# SPosition.net
KiCad netlist of a schematic drawn in EAGLE
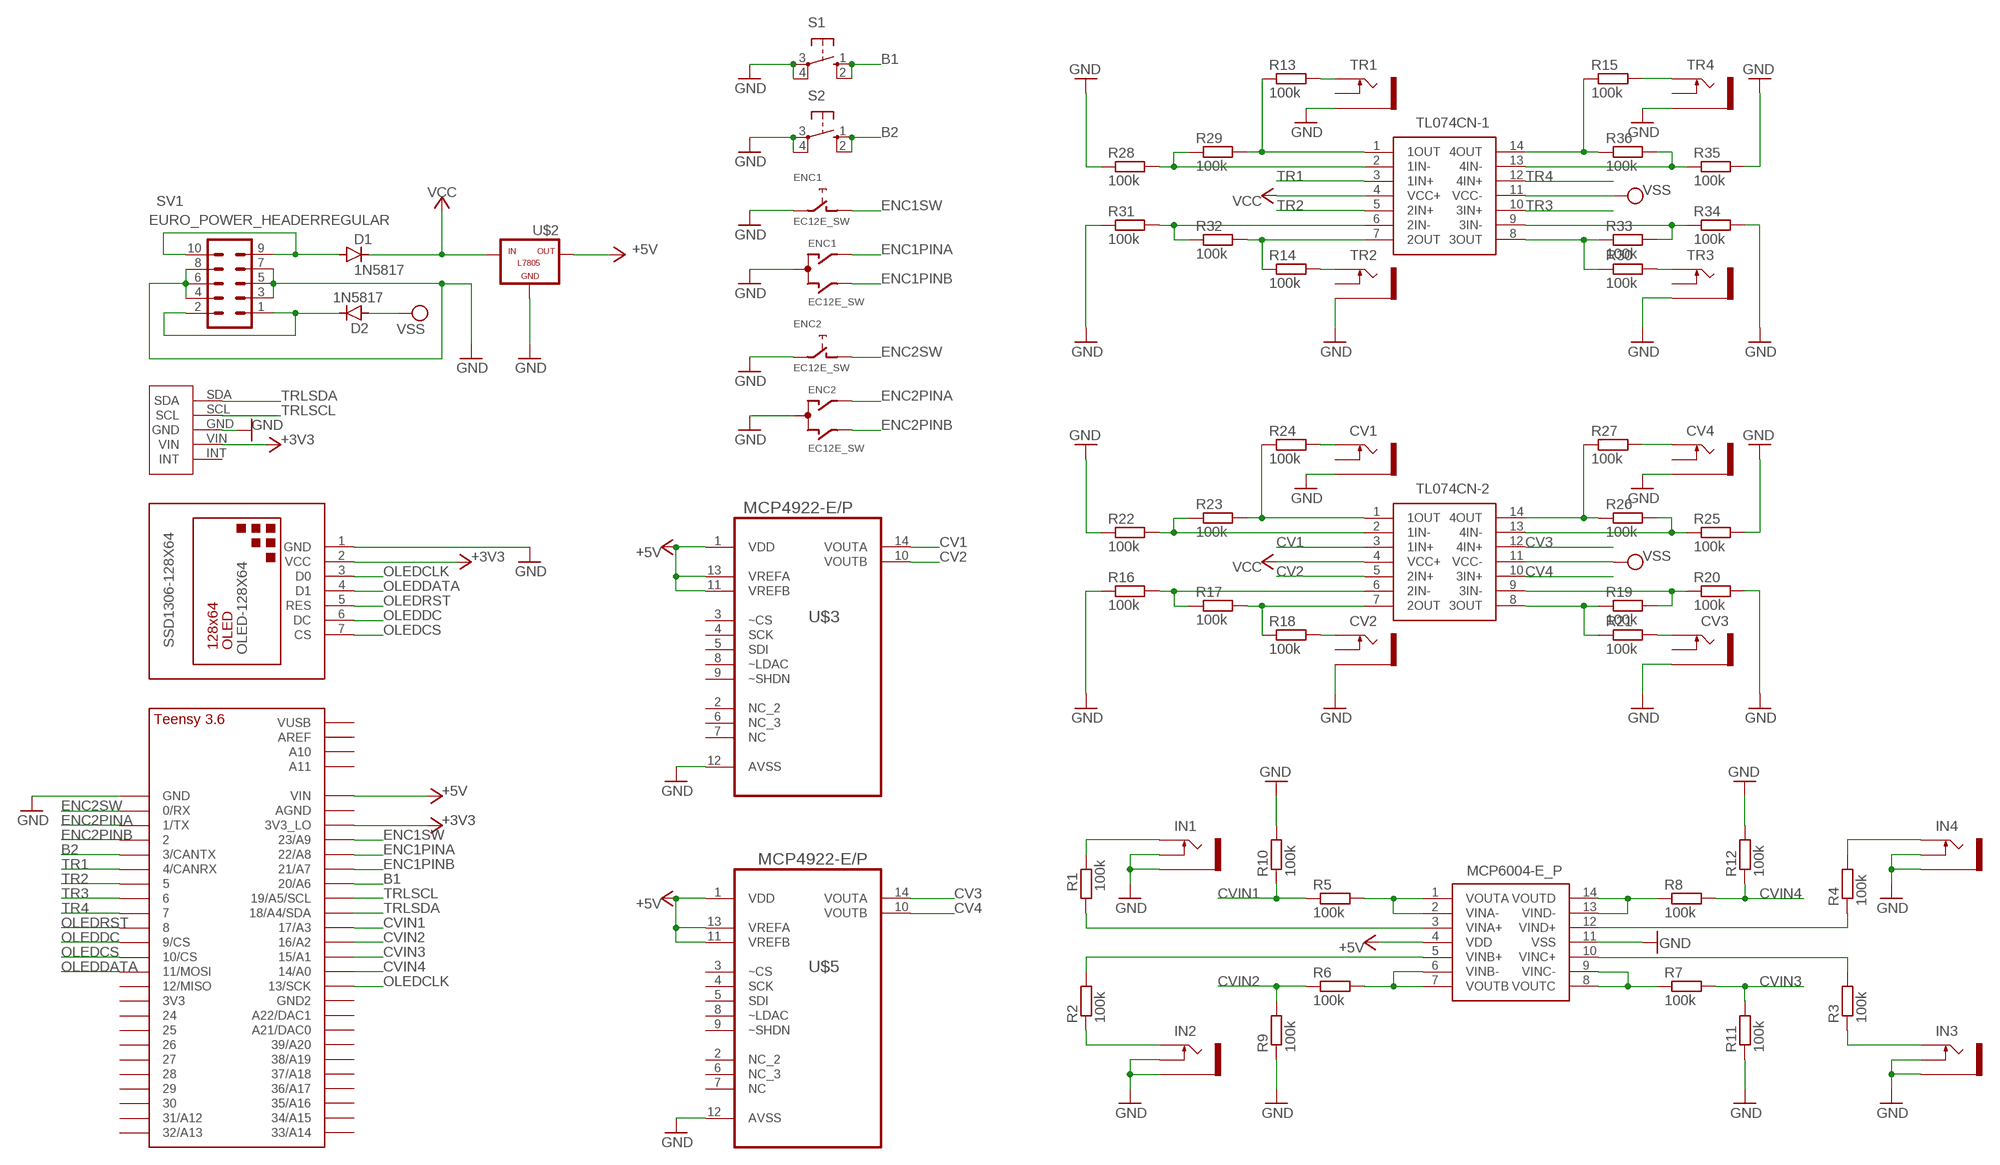
[diagram p0: schematic, sheet 1]

(export (version "E")
  (design (tool "Eeschema 10.0.6"))
  (components
    (comp (ref "CV1")
      (value "THONKICONNNEW")
      (footprint "eagle-import:WQP-PJ301M-12_JACK")
      (libsource (lib "eagle-import") (part "THONKICONNNEW"))
    )
    (comp (ref "CV2")
      (value "THONKICONNNEW")
      (footprint "eagle-import:WQP-PJ301M-12_JACK")
      (libsource (lib "eagle-import") (part "THONKICONNNEW"))
    )
    (comp (ref "CV3")
      (value "THONKICONNNEW")
      (footprint "eagle-import:WQP-PJ301M-12_JACK")
      (libsource (lib "eagle-import") (part "THONKICONNNEW"))
    )
    (comp (ref "CV4")
      (value "THONKICONNNEW")
      (footprint "eagle-import:WQP-PJ301M-12_JACK")
      (libsource (lib "eagle-import") (part "THONKICONNNEW"))
    )
    (comp (ref "D1")
      (value "1N5817")
      (footprint "eagle-import:DO41-10")
      (libsource (lib "eagle-import") (part "1N4004"))
    )
    (comp (ref "D2")
      (value "1N5817")
      (footprint "eagle-import:DO41-10")
      (libsource (lib "eagle-import") (part "1N4004"))
    )
    (comp (ref "ENC1")
      (value "EC12E_SW")
      (footprint "eagle-import:ALPS_EC12E_SW")
      (fields (field (name "MPN") "EC12E2424407"))
      (libsource (lib "eagle-import") (part "EC12E_SW"))
    )
    (comp (ref "ENC2")
      (value "EC12E_SW")
      (footprint "eagle-import:ALPS_EC12E_SW")
      (fields (field (name "MPN") "EC12E2424407"))
      (libsource (lib "eagle-import") (part "EC12E_SW"))
    )
    (comp (ref "IN1")
      (value "THONKICONNNEW")
      (footprint "eagle-import:WQP-PJ301M-12_JACK")
      (libsource (lib "eagle-import") (part "THONKICONNNEW"))
    )
    (comp (ref "IN2")
      (value "THONKICONNNEW")
      (footprint "eagle-import:WQP-PJ301M-12_JACK")
      (libsource (lib "eagle-import") (part "THONKICONNNEW"))
    )
    (comp (ref "IN3")
      (value "THONKICONNNEW")
      (footprint "eagle-import:WQP-PJ301M-12_JACK")
      (libsource (lib "eagle-import") (part "THONKICONNNEW"))
    )
    (comp (ref "IN4")
      (value "THONKICONNNEW")
      (footprint "eagle-import:WQP-PJ301M-12_JACK")
      (libsource (lib "eagle-import") (part "THONKICONNNEW"))
    )
    (comp (ref "MCP6004-E_P")
      (value "MCP6004-E_P")
      (footprint "eagle-import:DIP781W56P254L1918H533Q14N")
      (fields
        (field (name "MANUFACTURER_PART_NUMBER") "mcp6004-e/p")
        (field (name "MOUSER_PART_NUMBER") "579-MCP6004-E/P")
        (field (name "RS_PART_NUMBER") "7386178P")
      )
      (libsource (lib "eagle-import") (part "MCP6004-E_P"))
    )
    (comp (ref "R1")
      (value "100k")
      (footprint "eagle-import:R0805")
      (libsource (lib "eagle-import") (part "R-EU_R0805"))
    )
    (comp (ref "R2")
      (value "100k")
      (footprint "eagle-import:R0805")
      (libsource (lib "eagle-import") (part "R-EU_R0805"))
    )
    (comp (ref "R3")
      (value "100k")
      (footprint "eagle-import:R0805")
      (libsource (lib "eagle-import") (part "R-EU_R0805"))
    )
    (comp (ref "R4")
      (value "100k")
      (footprint "eagle-import:R0805")
      (libsource (lib "eagle-import") (part "R-EU_R0805"))
    )
    (comp (ref "R5")
      (value "100k")
      (footprint "eagle-import:R0805")
      (libsource (lib "eagle-import") (part "R-EU_R0805"))
    )
    (comp (ref "R6")
      (value "100k")
      (footprint "eagle-import:R0805")
      (libsource (lib "eagle-import") (part "R-EU_R0805"))
    )
    (comp (ref "R7")
      (value "100k")
      (footprint "eagle-import:R0805")
      (libsource (lib "eagle-import") (part "R-EU_R0805"))
    )
    (comp (ref "R8")
      (value "100k")
      (footprint "eagle-import:R0805")
      (libsource (lib "eagle-import") (part "R-EU_R0805"))
    )
    (comp (ref "R9")
      (value "100k")
      (footprint "eagle-import:R0805")
      (libsource (lib "eagle-import") (part "R-EU_R0805"))
    )
    (comp (ref "R10")
      (value "100k")
      (footprint "eagle-import:R0805")
      (libsource (lib "eagle-import") (part "R-EU_R0805"))
    )
    (comp (ref "R11")
      (value "100k")
      (footprint "eagle-import:R0805")
      (libsource (lib "eagle-import") (part "R-EU_R0805"))
    )
    (comp (ref "R12")
      (value "100k")
      (footprint "eagle-import:R0805")
      (libsource (lib "eagle-import") (part "R-EU_R0805"))
    )
    (comp (ref "R13")
      (value "100k")
      (footprint "eagle-import:R0805")
      (libsource (lib "eagle-import") (part "R-EU_R0805"))
    )
    (comp (ref "R14")
      (value "100k")
      (footprint "eagle-import:R0805")
      (libsource (lib "eagle-import") (part "R-EU_R0805"))
    )
    (comp (ref "R15")
      (value "100k")
      (footprint "eagle-import:R0805")
      (libsource (lib "eagle-import") (part "R-EU_R0805"))
    )
    (comp (ref "R16")
      (value "100k")
      (footprint "eagle-import:R0805")
      (libsource (lib "eagle-import") (part "R-EU_R0805"))
    )
    (comp (ref "R17")
      (value "100k")
      (footprint "eagle-import:R0805")
      (libsource (lib "eagle-import") (part "R-EU_R0805"))
    )
    (comp (ref "R18")
      (value "100k")
      (footprint "eagle-import:R0805")
      (libsource (lib "eagle-import") (part "R-EU_R0805"))
    )
    (comp (ref "R19")
      (value "100k")
      (footprint "eagle-import:R0805")
      (libsource (lib "eagle-import") (part "R-EU_R0805"))
    )
    (comp (ref "R20")
      (value "100k")
      (footprint "eagle-import:R0805")
      (libsource (lib "eagle-import") (part "R-EU_R0805"))
    )
    (comp (ref "R21")
      (value "100k")
      (footprint "eagle-import:R0805")
      (libsource (lib "eagle-import") (part "R-EU_R0805"))
    )
    (comp (ref "R22")
      (value "100k")
      (footprint "eagle-import:R0805")
      (libsource (lib "eagle-import") (part "R-EU_R0805"))
    )
    (comp (ref "R23")
      (value "100k")
      (footprint "eagle-import:R0805")
      (libsource (lib "eagle-import") (part "R-EU_R0805"))
    )
    (comp (ref "R24")
      (value "100k")
      (footprint "eagle-import:R0805")
      (libsource (lib "eagle-import") (part "R-EU_R0805"))
    )
    (comp (ref "R25")
      (value "100k")
      (footprint "eagle-import:R0805")
      (libsource (lib "eagle-import") (part "R-EU_R0805"))
    )
    (comp (ref "R26")
      (value "100k")
      (footprint "eagle-import:R0805")
      (libsource (lib "eagle-import") (part "R-EU_R0805"))
    )
    (comp (ref "R27")
      (value "100k")
      (footprint "eagle-import:R0805")
      (libsource (lib "eagle-import") (part "R-EU_R0805"))
    )
    (comp (ref "R28")
      (value "100k")
      (footprint "eagle-import:R0805")
      (libsource (lib "eagle-import") (part "R-EU_R0805"))
    )
    (comp (ref "R29")
      (value "100k")
      (footprint "eagle-import:R0805")
      (libsource (lib "eagle-import") (part "R-EU_R0805"))
    )
    (comp (ref "R30")
      (value "100k")
      (footprint "eagle-import:R0805")
      (libsource (lib "eagle-import") (part "R-EU_R0805"))
    )
    (comp (ref "R31")
      (value "100k")
      (footprint "eagle-import:R0805")
      (libsource (lib "eagle-import") (part "R-EU_R0805"))
    )
    (comp (ref "R32")
      (value "100k")
      (footprint "eagle-import:R0805")
      (libsource (lib "eagle-import") (part "R-EU_R0805"))
    )
    (comp (ref "R33")
      (value "100k")
      (footprint "eagle-import:R0805")
      (libsource (lib "eagle-import") (part "R-EU_R0805"))
    )
    (comp (ref "R34")
      (value "100k")
      (footprint "eagle-import:R0805")
      (libsource (lib "eagle-import") (part "R-EU_R0805"))
    )
    (comp (ref "R35")
      (value "100k")
      (footprint "eagle-import:R0805")
      (libsource (lib "eagle-import") (part "R-EU_R0805"))
    )
    (comp (ref "R36")
      (value "100k")
      (footprint "eagle-import:R0805")
      (libsource (lib "eagle-import") (part "R-EU_R0805"))
    )
    (comp (ref "S1")
      (value "10-XX")
      (footprint "eagle-import:B3F-10XX")
      (fields (field (name "MPN") "B3F-1000"))
      (libsource (lib "eagle-import") (part "10-XX"))
    )
    (comp (ref "S2")
      (value "10-XX")
      (footprint "eagle-import:B3F-10XX")
      (fields (field (name "MPN") "B3F-1000"))
      (libsource (lib "eagle-import") (part "10-XX"))
    )
    (comp (ref "SSD1306-128X64")
      (value "OLED-128X64")
      (footprint "eagle-import:DISPLAY-OLED-128X64-SMALL")
      (libsource (lib "eagle-import") (part "OLED-128X64"))
    )
    (comp (ref "SV1")
      (value "EURO_POWER_HEADERREGULAR")
      (footprint "eagle-import:EURO_POWER_HEADER")
      (libsource (lib "eagle-import") (part "EURO_POWER_HEADERREGULAR"))
    )
    (comp (ref "TL074CN-1")
      (value "TL074CN")
      (footprint "eagle-import:DIP794W53P254L1930H508Q14N")
      (fields (field (name "MOUSER_PART_NUMBER") "595-TL074CN") (field (name "RS_PART_NUMBER") "0302621P"))
      (libsource (lib "eagle-import") (part "TL074CN"))
    )
    (comp (ref "TL074CN-2")
      (value "TL074CN")
      (footprint "eagle-import:DIP794W53P254L1930H508Q14N")
      (fields (field (name "MOUSER_PART_NUMBER") "595-TL074CN") (field (name "RS_PART_NUMBER") "0302621P"))
      (libsource (lib "eagle-import") (part "TL074CN"))
    )
    (comp (ref "TR1")
      (value "THONKICONNNEW")
      (footprint "eagle-import:WQP-PJ301M-12_JACK")
      (libsource (lib "eagle-import") (part "THONKICONNNEW"))
    )
    (comp (ref "TR2")
      (value "THONKICONNNEW")
      (footprint "eagle-import:WQP-PJ301M-12_JACK")
      (libsource (lib "eagle-import") (part "THONKICONNNEW"))
    )
    (comp (ref "TR3")
      (value "THONKICONNNEW")
      (footprint "eagle-import:WQP-PJ301M-12_JACK")
      (libsource (lib "eagle-import") (part "THONKICONNNEW"))
    )
    (comp (ref "TR4")
      (value "THONKICONNNEW")
      (footprint "eagle-import:WQP-PJ301M-12_JACK")
      (libsource (lib "eagle-import") (part "THONKICONNNEW"))
    )
    (comp (ref "U$1")
      (value "TEENSY_3.5/3.6_BASIC")
      (footprint "eagle-import:TEENSY_3.5_3.6_BASIC")
      (libsource (lib "eagle-import") (part "TEENSY_3.5/3.6_BASIC"))
    )
    (comp (ref "U$2")
      (value "-L7805")
      (footprint "eagle-import:L7805")
      (libsource (lib "eagle-import") (part "-L7805"))
    )
    (comp (ref "U$3")
      (value "MCP4922-E/P")
      (footprint "eagle-import:DIP254P762X533-14")
      (fields (field (name "MF") "Microchip"))
      (libsource (lib "eagle-import") (part "MCP4922-E/P"))
    )
    (comp (ref "U$4")
      (value "SUPERPOSITION")
      (footprint "eagle-import:SUPERPOSITION")
      (libsource (lib "eagle-import") (part "SUPERPOSITION"))
    )
    (comp (ref "U$5")
      (value "MCP4922-E/P")
      (footprint "eagle-import:DIP254P762X533-14")
      (fields (field (name "MF") "Microchip"))
      (libsource (lib "eagle-import") (part "MCP4922-E/P"))
    )
  )
  (nets
    (net (code "1") (name "+3V3") (class "Default")
      (node (ref "SSD1306-128X64") (pin "2") (pinfunction "VCC_2") (pintype "power_in"))
      (node (ref "U$1") (pin "3V3_LO") (pinfunction "3V3_LO_3V3_LO") (pintype "bidirectional"))
      (node (ref "U$4") (pin "VIN") (pinfunction "VIN_VIN") (pintype "bidirectional"))
    )
    (net (code "2") (name "+5V") (class "Default")
      (node (ref "MCP6004-E_P") (pin "4") (pinfunction "VDD_4") (pintype "power_in"))
      (node (ref "U$1") (pin "VIN") (pinfunction "VIN_VIN") (pintype "bidirectional"))
      (node (ref "U$2") (pin "OUT") (pinfunction "OUT_OUT") (pintype "passive"))
      (node (ref "U$3") (pin "1") (pinfunction "VDD_1") (pintype "power_in"))
      (node (ref "U$3") (pin "11") (pinfunction "VREFB_11") (pintype "input"))
      (node (ref "U$3") (pin "13") (pinfunction "VREFA_13") (pintype "input"))
      (node (ref "U$5") (pin "1") (pinfunction "VDD_1") (pintype "power_in"))
      (node (ref "U$5") (pin "11") (pinfunction "VREFB_11") (pintype "input"))
      (node (ref "U$5") (pin "13") (pinfunction "VREFA_13") (pintype "input"))
    )
    (net (code "3") (name "/B1") (class "Default")
      (node (ref "S1") (pin "1") (pinfunction "S_1") (pintype "passive"))
      (node (ref "S1") (pin "2") (pinfunction "S1_2") (pintype "passive"))
      (node (ref "U$1") (pin "20/A6") (pinfunction "20/A6_20/A6") (pintype "bidirectional"))
    )
    (net (code "4") (name "/B2") (class "Default")
      (node (ref "S2") (pin "1") (pinfunction "S_1") (pintype "passive"))
      (node (ref "S2") (pin "2") (pinfunction "S1_2") (pintype "passive"))
      (node (ref "U$1") (pin "3/CANTX") (pinfunction "3/CANTX_3/CANTX") (pintype "bidirectional"))
    )
    (net (code "5") (name "/CV1") (class "Default")
      (node (ref "TL074CN-2") (pin "3") (pinfunction "1IN+_3") (pintype "input"))
      (node (ref "U$3") (pin "14") (pinfunction "VOUTA_14") (pintype "output"))
    )
    (net (code "6") (name "/CV2") (class "Default")
      (node (ref "TL074CN-2") (pin "5") (pinfunction "2IN+_5") (pintype "input"))
      (node (ref "U$3") (pin "10") (pinfunction "VOUTB_10") (pintype "output"))
    )
    (net (code "7") (name "/CV3") (class "Default")
      (node (ref "TL074CN-2") (pin "12") (pinfunction "4IN+_12") (pintype "input"))
      (node (ref "U$5") (pin "14") (pinfunction "VOUTA_14") (pintype "output"))
    )
    (net (code "8") (name "/CV4") (class "Default")
      (node (ref "TL074CN-2") (pin "10") (pinfunction "3IN+_10") (pintype "input"))
      (node (ref "U$5") (pin "10") (pinfunction "VOUTB_10") (pintype "output"))
    )
    (net (code "9") (name "/CVIN1") (class "Default")
      (node (ref "R10") (pin "1") (pinfunction "1_1") (pintype "passive"))
      (node (ref "R5") (pin "1") (pinfunction "1_1") (pintype "passive"))
      (node (ref "U$1") (pin "17/A3") (pinfunction "17/A3_17/A3") (pintype "bidirectional"))
    )
    (net (code "10") (name "/CVIN2") (class "Default")
      (node (ref "R6") (pin "1") (pinfunction "1_1") (pintype "passive"))
      (node (ref "R9") (pin "2") (pinfunction "2_2") (pintype "passive"))
      (node (ref "U$1") (pin "16/A2") (pinfunction "16/A2_16/A2") (pintype "bidirectional"))
    )
    (net (code "11") (name "/CVIN3") (class "Default")
      (node (ref "R11") (pin "2") (pinfunction "2_2") (pintype "passive"))
      (node (ref "R7") (pin "2") (pinfunction "2_2") (pintype "passive"))
      (node (ref "U$1") (pin "15/A1") (pinfunction "15/A1_15/A1") (pintype "bidirectional"))
    )
    (net (code "12") (name "/CVIN4") (class "Default")
      (node (ref "R12") (pin "1") (pinfunction "1_1") (pintype "passive"))
      (node (ref "R8") (pin "2") (pinfunction "2_2") (pintype "passive"))
      (node (ref "U$1") (pin "14/A0") (pinfunction "14/A0_14/A0") (pintype "bidirectional"))
    )
    (net (code "13") (name "/ENC1PINA") (class "Default")
      (node (ref "ENC1") (pin "A") (pinfunction "A_A") (pintype "passive"))
      (node (ref "U$1") (pin "22/A8") (pinfunction "22/A8_22/A8") (pintype "bidirectional"))
    )
    (net (code "14") (name "/ENC1PINB") (class "Default")
      (node (ref "ENC1") (pin "B") (pinfunction "B_B") (pintype "passive"))
      (node (ref "U$1") (pin "21/A7") (pinfunction "21/A7_21/A7") (pintype "bidirectional"))
    )
    (net (code "15") (name "/ENC1SW") (class "Default")
      (node (ref "ENC1") (pin "D") (pinfunction "1_D") (pintype "passive"))
      (node (ref "U$1") (pin "23/A9") (pinfunction "23/A9_23/A9") (pintype "bidirectional"))
    )
    (net (code "16") (name "/ENC2PINA") (class "Default")
      (node (ref "ENC2") (pin "A") (pinfunction "A_A") (pintype "passive"))
      (node (ref "U$1") (pin "1/TX") (pinfunction "1/TX_1/TX") (pintype "bidirectional"))
    )
    (net (code "17") (name "/ENC2PINB") (class "Default")
      (node (ref "ENC2") (pin "B") (pinfunction "B_B") (pintype "passive"))
      (node (ref "U$1") (pin "2") (pinfunction "2_2") (pintype "bidirectional"))
    )
    (net (code "18") (name "/ENC2SW") (class "Default")
      (node (ref "ENC2") (pin "D") (pinfunction "1_D") (pintype "passive"))
      (node (ref "U$1") (pin "0/RX") (pinfunction "0/RX_0/RX") (pintype "bidirectional"))
    )
    (net (code "19") (name "/OLEDCLK") (class "Default")
      (node (ref "SSD1306-128X64") (pin "3") (pinfunction "D0_3") (pintype "bidirectional"))
      (node (ref "U$1") (pin "13/SCK") (pinfunction "13/SCK_13/SCK") (pintype "bidirectional"))
    )
    (net (code "20") (name "/OLEDCS") (class "Default")
      (node (ref "SSD1306-128X64") (pin "7") (pinfunction "CS_7") (pintype "bidirectional"))
      (node (ref "U$1") (pin "10/CS") (pinfunction "10/CS_10/CS") (pintype "bidirectional"))
    )
    (net (code "21") (name "/OLEDDATA") (class "Default")
      (node (ref "SSD1306-128X64") (pin "4") (pinfunction "D1_4") (pintype "bidirectional"))
      (node (ref "U$1") (pin "11/MOSI") (pinfunction "11/MOSI_11/MOSI") (pintype "bidirectional"))
    )
    (net (code "22") (name "/OLEDDC") (class "Default")
      (node (ref "SSD1306-128X64") (pin "6") (pinfunction "DC_6") (pintype "bidirectional"))
      (node (ref "U$1") (pin "9/CS") (pinfunction "9/CS_9/CS") (pintype "bidirectional"))
    )
    (net (code "23") (name "/OLEDRST") (class "Default")
      (node (ref "SSD1306-128X64") (pin "5") (pinfunction "RES_5") (pintype "bidirectional"))
      (node (ref "U$1") (pin "8") (pinfunction "8_8") (pintype "bidirectional"))
    )
    (net (code "24") (name "/TR1") (class "Default")
      (node (ref "TL074CN-1") (pin "3") (pinfunction "1IN+_3") (pintype "input"))
      (node (ref "U$1") (pin "4/CANRX") (pinfunction "4/CANRX_4/CANRX") (pintype "bidirectional"))
    )
    (net (code "25") (name "/TR2") (class "Default")
      (node (ref "TL074CN-1") (pin "5") (pinfunction "2IN+_5") (pintype "input"))
      (node (ref "U$1") (pin "5") (pinfunction "5_5") (pintype "bidirectional"))
    )
    (net (code "26") (name "/TR3") (class "Default")
      (node (ref "TL074CN-1") (pin "10") (pinfunction "3IN+_10") (pintype "input"))
      (node (ref "U$1") (pin "6") (pinfunction "6_6") (pintype "bidirectional"))
    )
    (net (code "27") (name "/TR4") (class "Default")
      (node (ref "TL074CN-1") (pin "12") (pinfunction "4IN+_12") (pintype "input"))
      (node (ref "U$1") (pin "7") (pinfunction "7_7") (pintype "bidirectional"))
    )
    (net (code "28") (name "/TRLSCL") (class "Default")
      (node (ref "U$1") (pin "19/A5/SCL") (pinfunction "19/A5/SCL_19/A5/SCL") (pintype "bidirectional"))
      (node (ref "U$4") (pin "SCL") (pinfunction "SCL_SCL") (pintype "bidirectional"))
    )
    (net (code "29") (name "/TRLSDA") (class "Default")
      (node (ref "U$1") (pin "18/A4/SDA") (pinfunction "18/A4/SDA_18/A4/SDA") (pintype "bidirectional"))
      (node (ref "U$4") (pin "SDA") (pinfunction "SDA_SDA") (pintype "bidirectional"))
    )
    (net (code "30") (name "GND") (class "Default")
      (node (ref "CV1") (pin "P$3_SLEEVE") (pinfunction "SLEEVE_P$3_SLEEVE") (pintype "passive"))
      (node (ref "CV2") (pin "P$3_SLEEVE") (pinfunction "SLEEVE_P$3_SLEEVE") (pintype "passive"))
      (node (ref "CV3") (pin "P$3_SLEEVE") (pinfunction "SLEEVE_P$3_SLEEVE") (pintype "passive"))
      (node (ref "CV4") (pin "P$3_SLEEVE") (pinfunction "SLEEVE_P$3_SLEEVE") (pintype "passive"))
      (node (ref "ENC1") (pin "C") (pinfunction "C_C") (pintype "passive"))
      (node (ref "ENC1") (pin "E") (pinfunction "2_E") (pintype "passive"))
      (node (ref "ENC2") (pin "C") (pinfunction "C_C") (pintype "passive"))
      (node (ref "ENC2") (pin "E") (pinfunction "2_E") (pintype "passive"))
      (node (ref "IN1") (pin "P$2_SWITCH") (pinfunction "SWITCH_P$2_SWITCH") (pintype "passive"))
      (node (ref "IN1") (pin "P$3_SLEEVE") (pinfunction "SLEEVE_P$3_SLEEVE") (pintype "passive"))
      (node (ref "IN2") (pin "P$2_SWITCH") (pinfunction "SWITCH_P$2_SWITCH") (pintype "passive"))
      (node (ref "IN2") (pin "P$3_SLEEVE") (pinfunction "SLEEVE_P$3_SLEEVE") (pintype "passive"))
      (node (ref "IN3") (pin "P$2_SWITCH") (pinfunction "SWITCH_P$2_SWITCH") (pintype "passive"))
      (node (ref "IN3") (pin "P$3_SLEEVE") (pinfunction "SLEEVE_P$3_SLEEVE") (pintype "passive"))
      (node (ref "IN4") (pin "P$2_SWITCH") (pinfunction "SWITCH_P$2_SWITCH") (pintype "passive"))
      (node (ref "IN4") (pin "P$3_SLEEVE") (pinfunction "SLEEVE_P$3_SLEEVE") (pintype "passive"))
      (node (ref "MCP6004-E_P") (pin "11") (pinfunction "VSS_11") (pintype "power_in"))
      (node (ref "R10") (pin "2") (pinfunction "2_2") (pintype "passive"))
      (node (ref "R11") (pin "1") (pinfunction "1_1") (pintype "passive"))
      (node (ref "R12") (pin "2") (pinfunction "2_2") (pintype "passive"))
      (node (ref "R16") (pin "1") (pinfunction "1_1") (pintype "passive"))
      (node (ref "R20") (pin "2") (pinfunction "2_2") (pintype "passive"))
      (node (ref "R22") (pin "1") (pinfunction "1_1") (pintype "passive"))
      (node (ref "R25") (pin "2") (pinfunction "2_2") (pintype "passive"))
      (node (ref "R28") (pin "1") (pinfunction "1_1") (pintype "passive"))
      (node (ref "R31") (pin "1") (pinfunction "1_1") (pintype "passive"))
      (node (ref "R34") (pin "2") (pinfunction "2_2") (pintype "passive"))
      (node (ref "R35") (pin "2") (pinfunction "2_2") (pintype "passive"))
      (node (ref "R9") (pin "1") (pinfunction "1_1") (pintype "passive"))
      (node (ref "S1") (pin "3") (pinfunction "P_3") (pintype "passive"))
      (node (ref "S1") (pin "4") (pinfunction "P1_4") (pintype "passive"))
      (node (ref "S2") (pin "3") (pinfunction "P_3") (pintype "passive"))
      (node (ref "S2") (pin "4") (pinfunction "P1_4") (pintype "passive"))
      (node (ref "SSD1306-128X64") (pin "1") (pinfunction "GND_1") (pintype "power_in"))
      (node (ref "SV1") (pin "3") (pinfunction "3_3") (pintype "passive"))
      (node (ref "SV1") (pin "4") (pinfunction "4_4") (pintype "passive"))
      (node (ref "SV1") (pin "5") (pinfunction "5_5") (pintype "passive"))
      (node (ref "SV1") (pin "6") (pinfunction "6_6") (pintype "passive"))
      (node (ref "SV1") (pin "7") (pinfunction "7_7") (pintype "passive"))
      (node (ref "SV1") (pin "8") (pinfunction "8_8") (pintype "passive"))
      (node (ref "TR1") (pin "P$3_SLEEVE") (pinfunction "SLEEVE_P$3_SLEEVE") (pintype "passive"))
      (node (ref "TR2") (pin "P$3_SLEEVE") (pinfunction "SLEEVE_P$3_SLEEVE") (pintype "passive"))
      (node (ref "TR3") (pin "P$3_SLEEVE") (pinfunction "SLEEVE_P$3_SLEEVE") (pintype "passive"))
      (node (ref "TR4") (pin "P$3_SLEEVE") (pinfunction "SLEEVE_P$3_SLEEVE") (pintype "passive"))
      (node (ref "U$1") (pin "GND") (pinfunction "GND_GND") (pintype "bidirectional"))
      (node (ref "U$2") (pin "GND") (pinfunction "GND_GND") (pintype "input"))
      (node (ref "U$3") (pin "12") (pinfunction "AVSS_12") (pintype "power_in"))
      (node (ref "U$4") (pin "GND") (pinfunction "GND_GND") (pintype "bidirectional"))
      (node (ref "U$5") (pin "12") (pinfunction "AVSS_12") (pintype "power_in"))
    )
    (net (code "31") (name "Net-(CV1-TIP)") (class "Default")
      (node (ref "CV1") (pin "P$1_TIP") (pinfunction "TIP_P$1_TIP") (pintype "passive"))
      (node (ref "R24") (pin "2") (pinfunction "2_2") (pintype "passive"))
    )
    (net (code "32") (name "Net-(CV2-TIP)") (class "Default")
      (node (ref "CV2") (pin "P$1_TIP") (pinfunction "TIP_P$1_TIP") (pintype "passive"))
      (node (ref "R18") (pin "2") (pinfunction "2_2") (pintype "passive"))
    )
    (net (code "33") (name "Net-(CV3-TIP)") (class "Default")
      (node (ref "CV3") (pin "P$1_TIP") (pinfunction "TIP_P$1_TIP") (pintype "passive"))
      (node (ref "R21") (pin "2") (pinfunction "2_2") (pintype "passive"))
    )
    (net (code "34") (name "Net-(CV4-TIP)") (class "Default")
      (node (ref "CV4") (pin "P$1_TIP") (pinfunction "TIP_P$1_TIP") (pintype "passive"))
      (node (ref "R27") (pin "2") (pinfunction "2_2") (pintype "passive"))
    )
    (net (code "35") (name "Net-(D1-PadA)") (class "Default")
      (node (ref "D1") (pin "A") (pinfunction "A_A") (pintype "passive"))
      (node (ref "SV1") (pin "10") (pinfunction "10_10") (pintype "passive"))
      (node (ref "SV1") (pin "9") (pinfunction "9_9") (pintype "passive"))
    )
    (net (code "36") (name "Net-(D2-PadC)") (class "Default")
      (node (ref "D2") (pin "C") (pinfunction "C_C") (pintype "passive"))
      (node (ref "SV1") (pin "1") (pinfunction "1_1") (pintype "passive"))
      (node (ref "SV1") (pin "2") (pinfunction "2_2") (pintype "passive"))
    )
    (net (code "37") (name "Net-(IN1-TIP)") (class "Default")
      (node (ref "IN1") (pin "P$1_TIP") (pinfunction "TIP_P$1_TIP") (pintype "passive"))
      (node (ref "R1") (pin "2") (pinfunction "2_2") (pintype "passive"))
    )
    (net (code "38") (name "Net-(IN2-TIP)") (class "Default")
      (node (ref "IN2") (pin "P$1_TIP") (pinfunction "TIP_P$1_TIP") (pintype "passive"))
      (node (ref "R2") (pin "1") (pinfunction "1_1") (pintype "passive"))
    )
    (net (code "39") (name "Net-(IN3-TIP)") (class "Default")
      (node (ref "IN3") (pin "P$1_TIP") (pinfunction "TIP_P$1_TIP") (pintype "passive"))
      (node (ref "R3") (pin "1") (pinfunction "1_1") (pintype "passive"))
    )
    (net (code "40") (name "Net-(IN4-TIP)") (class "Default")
      (node (ref "IN4") (pin "P$1_TIP") (pinfunction "TIP_P$1_TIP") (pintype "passive"))
      (node (ref "R4") (pin "2") (pinfunction "2_2") (pintype "passive"))
    )
    (net (code "41") (name "Net-(MCP6004-E_P-VINA+)") (class "Default")
      (node (ref "MCP6004-E_P") (pin "3") (pinfunction "VINA+_3") (pintype "input"))
      (node (ref "R1") (pin "1") (pinfunction "1_1") (pintype "passive"))
    )
    (net (code "42") (name "Net-(MCP6004-E_P-VINA-)") (class "Default")
      (node (ref "MCP6004-E_P") (pin "1") (pinfunction "VOUTA_1") (pintype "output"))
      (node (ref "MCP6004-E_P") (pin "2") (pinfunction "VINA-_2") (pintype "input"))
      (node (ref "R5") (pin "2") (pinfunction "2_2") (pintype "passive"))
    )
    (net (code "43") (name "Net-(MCP6004-E_P-VINB+)") (class "Default")
      (node (ref "MCP6004-E_P") (pin "5") (pinfunction "VINB+_5") (pintype "input"))
      (node (ref "R2") (pin "2") (pinfunction "2_2") (pintype "passive"))
    )
    (net (code "44") (name "Net-(MCP6004-E_P-VINB-)") (class "Default")
      (node (ref "MCP6004-E_P") (pin "6") (pinfunction "VINB-_6") (pintype "input"))
      (node (ref "MCP6004-E_P") (pin "7") (pinfunction "VOUTB_7") (pintype "output"))
      (node (ref "R6") (pin "2") (pinfunction "2_2") (pintype "passive"))
    )
    (net (code "45") (name "Net-(MCP6004-E_P-VINC+)") (class "Default")
      (node (ref "MCP6004-E_P") (pin "10") (pinfunction "VINC+_10") (pintype "input"))
      (node (ref "R3") (pin "2") (pinfunction "2_2") (pintype "passive"))
    )
    (net (code "46") (name "Net-(MCP6004-E_P-VINC-)") (class "Default")
      (node (ref "MCP6004-E_P") (pin "8") (pinfunction "VOUTC_8") (pintype "output"))
      (node (ref "MCP6004-E_P") (pin "9") (pinfunction "VINC-_9") (pintype "input"))
      (node (ref "R7") (pin "1") (pinfunction "1_1") (pintype "passive"))
    )
    (net (code "47") (name "Net-(MCP6004-E_P-VIND+)") (class "Default")
      (node (ref "MCP6004-E_P") (pin "12") (pinfunction "VIND+_12") (pintype "input"))
      (node (ref "R4") (pin "1") (pinfunction "1_1") (pintype "passive"))
    )
    (net (code "48") (name "Net-(MCP6004-E_P-VIND-)") (class "Default")
      (node (ref "MCP6004-E_P") (pin "13") (pinfunction "VIND-_13") (pintype "input"))
      (node (ref "MCP6004-E_P") (pin "14") (pinfunction "VOUTD_14") (pintype "output"))
      (node (ref "R8") (pin "1") (pinfunction "1_1") (pintype "passive"))
    )
    (net (code "49") (name "Net-(TL074CN-1-1IN-)") (class "Default")
      (node (ref "R28") (pin "2") (pinfunction "2_2") (pintype "passive"))
      (node (ref "R29") (pin "1") (pinfunction "1_1") (pintype "passive"))
      (node (ref "TL074CN-1") (pin "2") (pinfunction "1IN-_2") (pintype "input"))
    )
    (net (code "50") (name "Net-(TL074CN-1-1OUT)") (class "Default")
      (node (ref "R13") (pin "1") (pinfunction "1_1") (pintype "passive"))
      (node (ref "R29") (pin "2") (pinfunction "2_2") (pintype "passive"))
      (node (ref "TL074CN-1") (pin "1") (pinfunction "1OUT_1") (pintype "output"))
    )
    (net (code "51") (name "Net-(TL074CN-1-2IN-)") (class "Default")
      (node (ref "R31") (pin "2") (pinfunction "2_2") (pintype "passive"))
      (node (ref "R32") (pin "1") (pinfunction "1_1") (pintype "passive"))
      (node (ref "TL074CN-1") (pin "6") (pinfunction "2IN-_6") (pintype "input"))
    )
    (net (code "52") (name "Net-(TL074CN-1-2OUT)") (class "Default")
      (node (ref "R14") (pin "1") (pinfunction "1_1") (pintype "passive"))
      (node (ref "R32") (pin "2") (pinfunction "2_2") (pintype "passive"))
      (node (ref "TL074CN-1") (pin "7") (pinfunction "2OUT_7") (pintype "output"))
    )
    (net (code "53") (name "Net-(TL074CN-1-3IN-)") (class "Default")
      (node (ref "R33") (pin "2") (pinfunction "2_2") (pintype "passive"))
      (node (ref "R34") (pin "1") (pinfunction "1_1") (pintype "passive"))
      (node (ref "TL074CN-1") (pin "9") (pinfunction "3IN-_9") (pintype "input"))
    )
    (net (code "54") (name "Net-(TL074CN-1-3OUT)") (class "Default")
      (node (ref "R30") (pin "1") (pinfunction "1_1") (pintype "passive"))
      (node (ref "R33") (pin "1") (pinfunction "1_1") (pintype "passive"))
      (node (ref "TL074CN-1") (pin "8") (pinfunction "3OUT_8") (pintype "output"))
    )
    (net (code "55") (name "Net-(TL074CN-1-4IN-)") (class "Default")
      (node (ref "R35") (pin "1") (pinfunction "1_1") (pintype "passive"))
      (node (ref "R36") (pin "2") (pinfunction "2_2") (pintype "passive"))
      (node (ref "TL074CN-1") (pin "13") (pinfunction "4IN-_13") (pintype "input"))
    )
    (net (code "56") (name "Net-(TL074CN-1-4OUT)") (class "Default")
      (node (ref "R15") (pin "1") (pinfunction "1_1") (pintype "passive"))
      (node (ref "R36") (pin "1") (pinfunction "1_1") (pintype "passive"))
      (node (ref "TL074CN-1") (pin "14") (pinfunction "4OUT_14") (pintype "output"))
    )
    (net (code "57") (name "Net-(TL074CN-2-1IN-)") (class "Default")
      (node (ref "R22") (pin "2") (pinfunction "2_2") (pintype "passive"))
      (node (ref "R23") (pin "1") (pinfunction "1_1") (pintype "passive"))
      (node (ref "TL074CN-2") (pin "2") (pinfunction "1IN-_2") (pintype "input"))
    )
    (net (code "58") (name "Net-(TL074CN-2-1OUT)") (class "Default")
      (node (ref "R23") (pin "2") (pinfunction "2_2") (pintype "passive"))
      (node (ref "R24") (pin "1") (pinfunction "1_1") (pintype "passive"))
      (node (ref "TL074CN-2") (pin "1") (pinfunction "1OUT_1") (pintype "output"))
    )
    (net (code "59") (name "Net-(TL074CN-2-2IN-)") (class "Default")
      (node (ref "R16") (pin "2") (pinfunction "2_2") (pintype "passive"))
      (node (ref "R17") (pin "1") (pinfunction "1_1") (pintype "passive"))
      (node (ref "TL074CN-2") (pin "6") (pinfunction "2IN-_6") (pintype "input"))
    )
    (net (code "60") (name "Net-(TL074CN-2-2OUT)") (class "Default")
      (node (ref "R17") (pin "2") (pinfunction "2_2") (pintype "passive"))
      (node (ref "R18") (pin "1") (pinfunction "1_1") (pintype "passive"))
      (node (ref "TL074CN-2") (pin "7") (pinfunction "2OUT_7") (pintype "output"))
    )
    (net (code "61") (name "Net-(TL074CN-2-3IN-)") (class "Default")
      (node (ref "R19") (pin "2") (pinfunction "2_2") (pintype "passive"))
      (node (ref "R20") (pin "1") (pinfunction "1_1") (pintype "passive"))
      (node (ref "TL074CN-2") (pin "9") (pinfunction "3IN-_9") (pintype "input"))
    )
    (net (code "62") (name "Net-(TL074CN-2-3OUT)") (class "Default")
      (node (ref "R19") (pin "1") (pinfunction "1_1") (pintype "passive"))
      (node (ref "R21") (pin "1") (pinfunction "1_1") (pintype "passive"))
      (node (ref "TL074CN-2") (pin "8") (pinfunction "3OUT_8") (pintype "output"))
    )
    (net (code "63") (name "Net-(TL074CN-2-4IN-)") (class "Default")
      (node (ref "R25") (pin "1") (pinfunction "1_1") (pintype "passive"))
      (node (ref "R26") (pin "2") (pinfunction "2_2") (pintype "passive"))
      (node (ref "TL074CN-2") (pin "13") (pinfunction "4IN-_13") (pintype "input"))
    )
    (net (code "64") (name "Net-(TL074CN-2-4OUT)") (class "Default")
      (node (ref "R26") (pin "1") (pinfunction "1_1") (pintype "passive"))
      (node (ref "R27") (pin "1") (pinfunction "1_1") (pintype "passive"))
      (node (ref "TL074CN-2") (pin "14") (pinfunction "4OUT_14") (pintype "output"))
    )
    (net (code "65") (name "Net-(TR1-TIP)") (class "Default")
      (node (ref "R13") (pin "2") (pinfunction "2_2") (pintype "passive"))
      (node (ref "TR1") (pin "P$1_TIP") (pinfunction "TIP_P$1_TIP") (pintype "passive"))
    )
    (net (code "66") (name "Net-(TR2-TIP)") (class "Default")
      (node (ref "R14") (pin "2") (pinfunction "2_2") (pintype "passive"))
      (node (ref "TR2") (pin "P$1_TIP") (pinfunction "TIP_P$1_TIP") (pintype "passive"))
    )
    (net (code "67") (name "Net-(TR3-TIP)") (class "Default")
      (node (ref "R30") (pin "2") (pinfunction "2_2") (pintype "passive"))
      (node (ref "TR3") (pin "P$1_TIP") (pinfunction "TIP_P$1_TIP") (pintype "passive"))
    )
    (net (code "68") (name "Net-(TR4-TIP)") (class "Default")
      (node (ref "R15") (pin "2") (pinfunction "2_2") (pintype "passive"))
      (node (ref "TR4") (pin "P$1_TIP") (pinfunction "TIP_P$1_TIP") (pintype "passive"))
    )
    (net (code "69") (name "VCC") (class "Default")
      (node (ref "D1") (pin "C") (pinfunction "C_C") (pintype "passive"))
      (node (ref "TL074CN-1") (pin "4") (pinfunction "VCC+_4") (pintype "power_in"))
      (node (ref "TL074CN-2") (pin "4") (pinfunction "VCC+_4") (pintype "power_in"))
      (node (ref "U$2") (pin "IN") (pinfunction "IN_IN") (pintype "input"))
    )
    (net (code "70") (name "VSS") (class "Default")
      (node (ref "D2") (pin "A") (pinfunction "A_A") (pintype "passive"))
      (node (ref "TL074CN-1") (pin "11") (pinfunction "VCC-_11") (pintype "power_in"))
      (node (ref "TL074CN-2") (pin "11") (pinfunction "VCC-_11") (pintype "power_in"))
    )
    (net (code "71") (name "unconnected-(CV1-SWITCH-PadP$2_SWITCH)") (class "Default")
      (node (ref "CV1") (pin "P$2_SWITCH") (pinfunction "SWITCH_P$2_SWITCH") (pintype "passive"))
    )
    (net (code "72") (name "unconnected-(CV2-SWITCH-PadP$2_SWITCH)") (class "Default")
      (node (ref "CV2") (pin "P$2_SWITCH") (pinfunction "SWITCH_P$2_SWITCH") (pintype "passive"))
    )
    (net (code "73") (name "unconnected-(CV3-SWITCH-PadP$2_SWITCH)") (class "Default")
      (node (ref "CV3") (pin "P$2_SWITCH") (pinfunction "SWITCH_P$2_SWITCH") (pintype "passive"))
    )
    (net (code "74") (name "unconnected-(CV4-SWITCH-PadP$2_SWITCH)") (class "Default")
      (node (ref "CV4") (pin "P$2_SWITCH") (pinfunction "SWITCH_P$2_SWITCH") (pintype "passive"))
    )
    (net (code "75") (name "unconnected-(TR1-SWITCH-PadP$2_SWITCH)") (class "Default")
      (node (ref "TR1") (pin "P$2_SWITCH") (pinfunction "SWITCH_P$2_SWITCH") (pintype "passive"))
    )
    (net (code "76") (name "unconnected-(TR2-SWITCH-PadP$2_SWITCH)") (class "Default")
      (node (ref "TR2") (pin "P$2_SWITCH") (pinfunction "SWITCH_P$2_SWITCH") (pintype "passive"))
    )
    (net (code "77") (name "unconnected-(TR3-SWITCH-PadP$2_SWITCH)") (class "Default")
      (node (ref "TR3") (pin "P$2_SWITCH") (pinfunction "SWITCH_P$2_SWITCH") (pintype "passive"))
    )
    (net (code "78") (name "unconnected-(TR4-SWITCH-PadP$2_SWITCH)") (class "Default")
      (node (ref "TR4") (pin "P$2_SWITCH") (pinfunction "SWITCH_P$2_SWITCH") (pintype "passive"))
    )
    (net (code "79") (name "unconnected-(U$1-A21{slash}DAC0-Pad21{slash}DAC0)") (class "Default")
      (node (ref "U$1") (pin "21/DAC0") (pinfunction "A21/DAC0_21/DAC0") (pintype "bidirectional"))
    )
    (net (code "80") (name "unconnected-(U$1-Pad3V3)") (class "Default")
      (node (ref "U$1") (pin "3V3") (pinfunction "3V3_3V3") (pintype "bidirectional"))
    )
    (net (code "81") (name "unconnected-(U$1-Pad12{slash}MISO)") (class "Default")
      (node (ref "U$1") (pin "12/MISO") (pinfunction "12/MISO_12/MISO") (pintype "bidirectional"))
    )
    (net (code "82") (name "unconnected-(U$1-Pad24)") (class "Default")
      (node (ref "U$1") (pin "24") (pinfunction "24_24") (pintype "bidirectional"))
    )
    (net (code "83") (name "unconnected-(U$1-Pad25)") (class "Default")
      (node (ref "U$1") (pin "25") (pinfunction "25_25") (pintype "bidirectional"))
    )
    (net (code "84") (name "unconnected-(U$1-Pad26)") (class "Default")
      (node (ref "U$1") (pin "26") (pinfunction "26_26") (pintype "bidirectional"))
    )
    (net (code "85") (name "unconnected-(U$1-Pad27)") (class "Default")
      (node (ref "U$1") (pin "27") (pinfunction "27_27") (pintype "bidirectional"))
    )
    (net (code "86") (name "unconnected-(U$1-Pad28)") (class "Default")
      (node (ref "U$1") (pin "28") (pinfunction "28_28") (pintype "bidirectional"))
    )
    (net (code "87") (name "unconnected-(U$1-Pad29)") (class "Default")
      (node (ref "U$1") (pin "29") (pinfunction "29_29") (pintype "bidirectional"))
    )
    (net (code "88") (name "unconnected-(U$1-Pad30)") (class "Default")
      (node (ref "U$1") (pin "30") (pinfunction "30_30") (pintype "bidirectional"))
    )
    (net (code "89") (name "unconnected-(U$1-Pad31{slash}A12)") (class "Default")
      (node (ref "U$1") (pin "31/A12") (pinfunction "31/A12_31/A12") (pintype "bidirectional"))
    )
    (net (code "90") (name "unconnected-(U$1-Pad32{slash}A13)") (class "Default")
      (node (ref "U$1") (pin "32/A13") (pinfunction "32/A13_32/A13") (pintype "bidirectional"))
    )
    (net (code "91") (name "unconnected-(U$1-Pad33{slash}A14)") (class "Default")
      (node (ref "U$1") (pin "33/A14") (pinfunction "33/A14_33/A14") (pintype "bidirectional"))
    )
    (net (code "92") (name "unconnected-(U$1-Pad34{slash}A15)") (class "Default")
      (node (ref "U$1") (pin "34/A15") (pinfunction "34/A15_34/A15") (pintype "bidirectional"))
    )
    (net (code "93") (name "unconnected-(U$1-Pad35{slash}A16)") (class "Default")
      (node (ref "U$1") (pin "35/A16") (pinfunction "35/A16_35/A16") (pintype "bidirectional"))
    )
    (net (code "94") (name "unconnected-(U$1-Pad36{slash}A17)") (class "Default")
      (node (ref "U$1") (pin "36/A17") (pinfunction "36/A17_36/A17") (pintype "bidirectional"))
    )
    (net (code "95") (name "unconnected-(U$1-Pad37{slash}A18)") (class "Default")
      (node (ref "U$1") (pin "37/A18") (pinfunction "37/A18_37/A18") (pintype "bidirectional"))
    )
    (net (code "96") (name "unconnected-(U$1-Pad38{slash}A19)") (class "Default")
      (node (ref "U$1") (pin "38/A19") (pinfunction "38/A19_38/A19") (pintype "bidirectional"))
    )
    (net (code "97") (name "unconnected-(U$1-Pad39{slash}A20)") (class "Default")
      (node (ref "U$1") (pin "39/A20") (pinfunction "39/A20_39/A20") (pintype "bidirectional"))
    )
    (net (code "98") (name "unconnected-(U$1-PadA10)") (class "Default")
      (node (ref "U$1") (pin "A10") (pinfunction "A10_A10") (pintype "bidirectional"))
    )
    (net (code "99") (name "unconnected-(U$1-PadA11)") (class "Default")
      (node (ref "U$1") (pin "A11") (pinfunction "A11_A11") (pintype "bidirectional"))
    )
    (net (code "100") (name "unconnected-(U$1-PadA22{slash}DAC1)") (class "Default")
      (node (ref "U$1") (pin "A22/DAC1") (pinfunction "A22/DAC1_A22/DAC1") (pintype "bidirectional"))
    )
    (net (code "101") (name "unconnected-(U$1-PadAGND)") (class "Default")
      (node (ref "U$1") (pin "AGND") (pinfunction "AGND_AGND") (pintype "bidirectional"))
    )
    (net (code "102") (name "unconnected-(U$1-PadAREF)") (class "Default")
      (node (ref "U$1") (pin "AREF") (pinfunction "AREF_AREF") (pintype "bidirectional"))
    )
    (net (code "103") (name "unconnected-(U$1-PadGND2)") (class "Default")
      (node (ref "U$1") (pin "GND2") (pinfunction "GND2_GND2") (pintype "bidirectional"))
    )
    (net (code "104") (name "unconnected-(U$1-PadVUSB)") (class "Default")
      (node (ref "U$1") (pin "VUSB") (pinfunction "VUSB_VUSB") (pintype "bidirectional"))
    )
    (net (code "105") (name "unconnected-(U$3-NC-Pad7)") (class "Default")
      (node (ref "U$3") (pin "7") (pinfunction "NC_7") (pintype "no_connect"))
    )
    (net (code "106") (name "unconnected-(U$3-NC_2-Pad2)") (class "Default")
      (node (ref "U$3") (pin "2") (pinfunction "NC_2_2") (pintype "no_connect"))
    )
    (net (code "107") (name "unconnected-(U$3-NC_3-Pad6)") (class "Default")
      (node (ref "U$3") (pin "6") (pinfunction "NC_3_6") (pintype "no_connect"))
    )
    (net (code "108") (name "unconnected-(U$3-SCK-Pad4)") (class "Default")
      (node (ref "U$3") (pin "4") (pinfunction "SCK_4") (pintype "input"))
    )
    (net (code "109") (name "unconnected-(U$3-SDI-Pad5)") (class "Default")
      (node (ref "U$3") (pin "5") (pinfunction "SDI_5") (pintype "input"))
    )
    (net (code "110") (name "unconnected-(U$3-~{CS}-Pad3)") (class "Default")
      (node (ref "U$3") (pin "3") (pinfunction "~{CS}_3") (pintype "input"))
    )
    (net (code "111") (name "unconnected-(U$3-~{LDAC}-Pad8)") (class "Default")
      (node (ref "U$3") (pin "8") (pinfunction "~{LDAC}_8") (pintype "input"))
    )
    (net (code "112") (name "unconnected-(U$3-~{SHDN}-Pad9)") (class "Default")
      (node (ref "U$3") (pin "9") (pinfunction "~{SHDN}_9") (pintype "input"))
    )
    (net (code "113") (name "unconnected-(U$4-PadINT)") (class "Default")
      (node (ref "U$4") (pin "INT") (pinfunction "INT_INT") (pintype "bidirectional"))
    )
    (net (code "114") (name "unconnected-(U$5-NC-Pad7)") (class "Default")
      (node (ref "U$5") (pin "7") (pinfunction "NC_7") (pintype "no_connect"))
    )
    (net (code "115") (name "unconnected-(U$5-NC_2-Pad2)") (class "Default")
      (node (ref "U$5") (pin "2") (pinfunction "NC_2_2") (pintype "no_connect"))
    )
    (net (code "116") (name "unconnected-(U$5-NC_3-Pad6)") (class "Default")
      (node (ref "U$5") (pin "6") (pinfunction "NC_3_6") (pintype "no_connect"))
    )
    (net (code "117") (name "unconnected-(U$5-SCK-Pad4)") (class "Default")
      (node (ref "U$5") (pin "4") (pinfunction "SCK_4") (pintype "input"))
    )
    (net (code "118") (name "unconnected-(U$5-SDI-Pad5)") (class "Default")
      (node (ref "U$5") (pin "5") (pinfunction "SDI_5") (pintype "input"))
    )
    (net (code "119") (name "unconnected-(U$5-~{CS}-Pad3)") (class "Default")
      (node (ref "U$5") (pin "3") (pinfunction "~{CS}_3") (pintype "input"))
    )
    (net (code "120") (name "unconnected-(U$5-~{LDAC}-Pad8)") (class "Default")
      (node (ref "U$5") (pin "8") (pinfunction "~{LDAC}_8") (pintype "input"))
    )
    (net (code "121") (name "unconnected-(U$5-~{SHDN}-Pad9)") (class "Default")
      (node (ref "U$5") (pin "9") (pinfunction "~{SHDN}_9") (pintype "input"))
    )
  )
)
